# PwrPiSchematics.net
KiCad netlist of a schematic drawn in EasyEDA
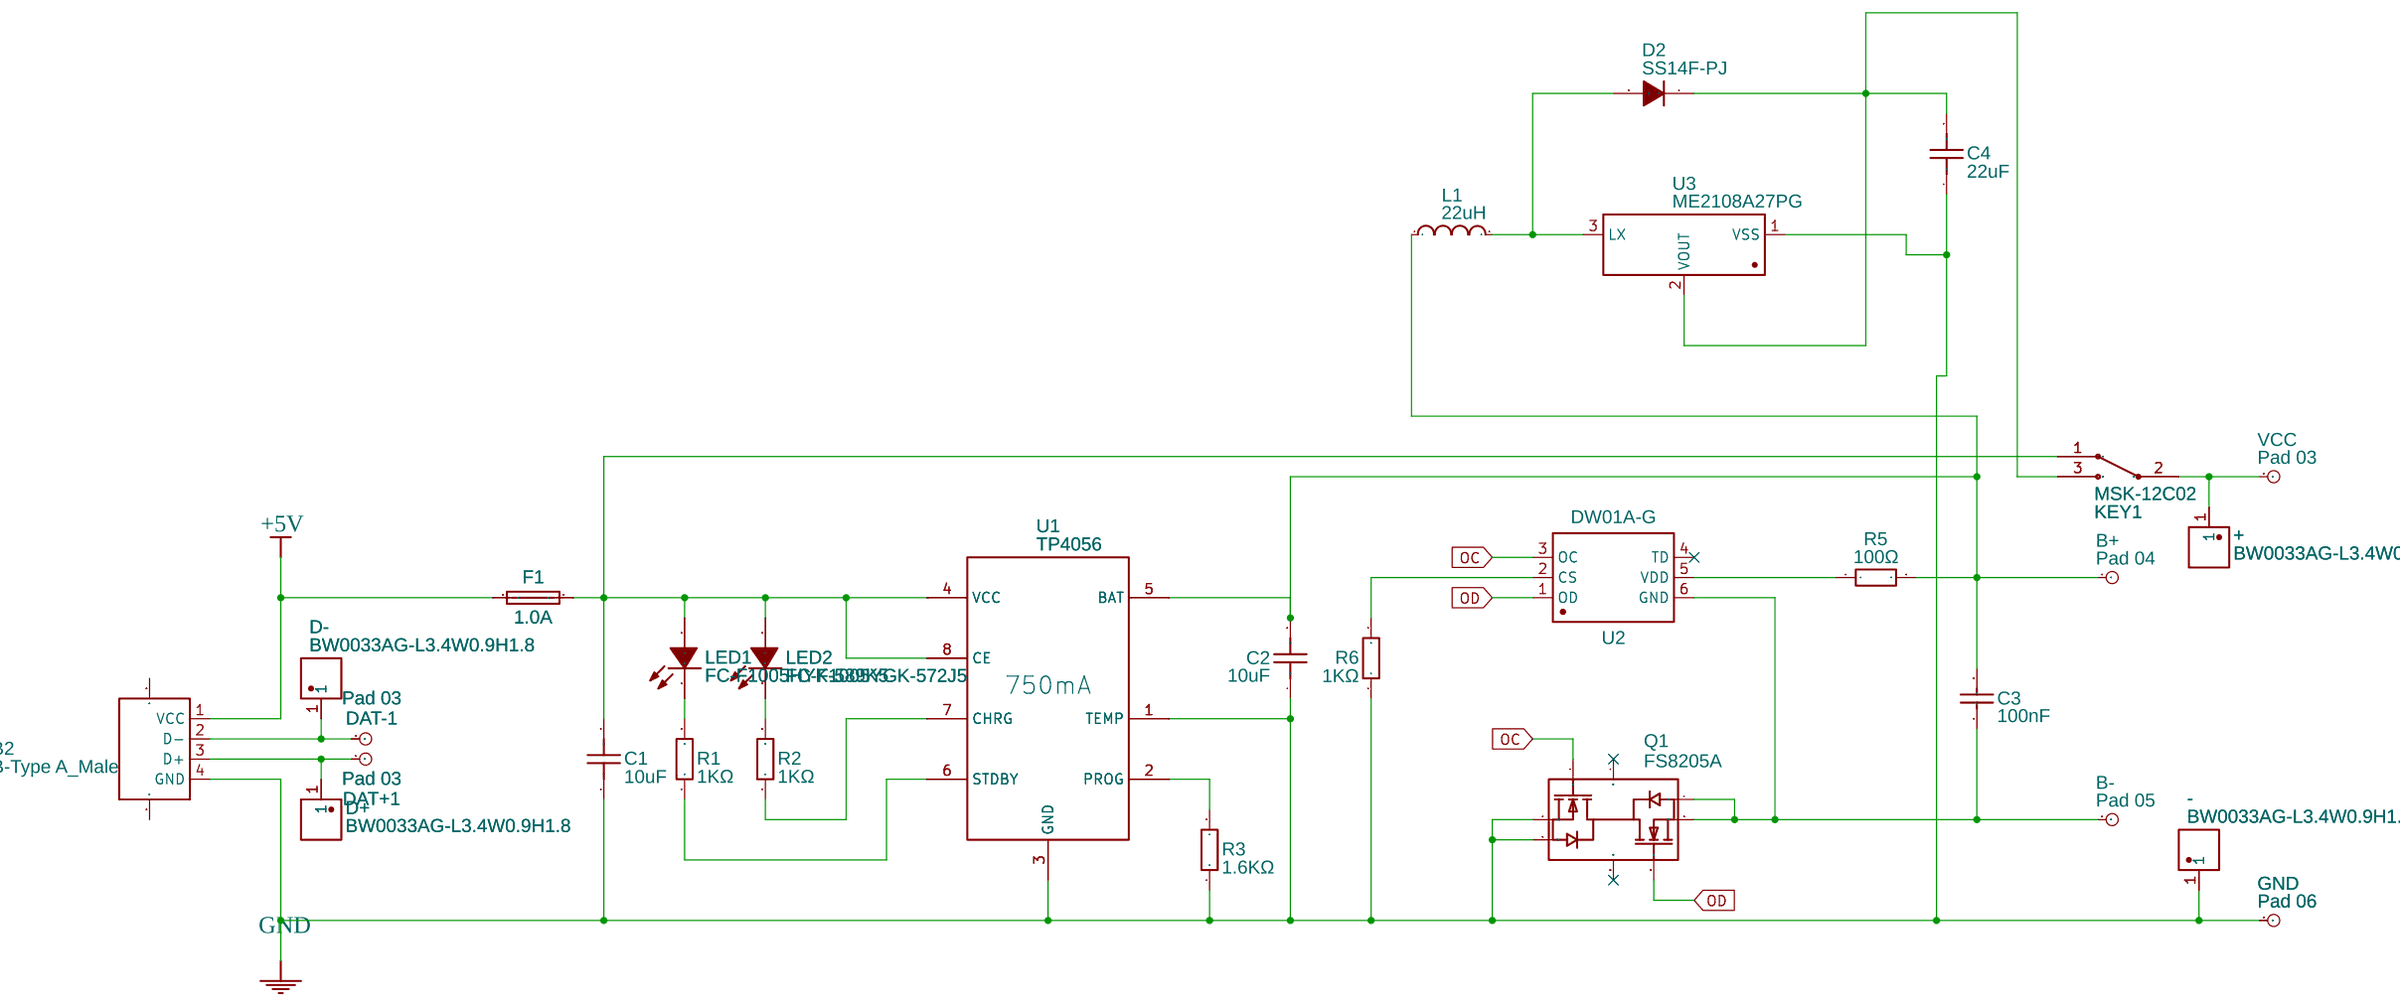
[diagram p0: schematic sheet]

(export (version "E")
  (design (tool "Eeschema 10.0.6"))
  (components
    (comp (ref "+")
      (value "BW0033AG-L3.4W0.9H1.8")
      (fields (field (name "Manufacturer") "BAT WIRELESS(蝙蝠无线)"))
      (libsource (lib "") (part "BW0033AG-L3.4W0.9H1.8_2"))
    )
    (comp (ref "-")
      (value "BW0033AG-L3.4W0.9H1.8")
      (fields (field (name "Manufacturer") "BAT WIRELESS(蝙蝠无线)"))
      (libsource (lib "") (part "BW0033AG-L3.4W0.9H1.8"))
    )
    (comp (ref "B+")
      (value "Pad 04")
      (fields (field (name "Manufacturer Part") "?"))
      (libsource (lib "") (part "Unknown_410_70"))
    )
    (comp (ref "B-")
      (value "Pad 05")
      (fields (field (name "Manufacturer Part") "?"))
      (libsource (lib "") (part "Unknown_410_190"))
    )
    (comp (ref "C1")
      (value "10uF")
      (fields (field (name "Manufacturer Part") "CL10A106MA8NRNC") (field (name "Manufacturer") "SAMSUNG"))
      (libsource (lib "") (part "CL10A106MA8NRNC"))
    )
    (comp (ref "C2")
      (value "10uF")
      (fields (field (name "Manufacturer Part") "CL10A106MA8NRNC") (field (name "Manufacturer") "SAMSUNG"))
      (libsource (lib "") (part "CL10A106MA8NRNC_1"))
    )
    (comp (ref "C3")
      (value "100nF")
      (fields (field (name "Manufacturer Part") "CL05B104KO5NNNC") (field (name "Manufacturer") "SAMSUNG"))
      (libsource (lib "") (part "CL05B104KO5NNNC"))
    )
    (comp (ref "C4")
      (value "22uF")
      (fields
        (field (name "Manufacturer Part") "GRM188R60J226MEA0D")
        (field (name "Manufacturer") "muRata(村田)")
      )
      (libsource (lib "") (part "GRM188R60J226MEA0D"))
    )
    (comp (ref "D+")
      (value "BW0033AG-L3.4W0.9H1.8")
      (fields (field (name "Manufacturer") "BAT WIRELESS(蝙蝠无线)"))
      (libsource (lib "") (part "BW0033AG-L3.4W0.9H1.8_3"))
    )
    (comp (ref "D-")
      (value "BW0033AG-L3.4W0.9H1.8")
      (fields (field (name "Manufacturer") "BAT WIRELESS(蝙蝠无线)"))
      (libsource (lib "") (part "BW0033AG-L3.4W0.9H1.8_1"))
    )
    (comp (ref "D2")
      (value "SS14F-PJ")
      (fields (field (name "Manufacturer") "PJSEMI(平晶微)"))
      (libsource (lib "") (part "SS14F-PJ"))
    )
    (comp (ref "DAT+1")
      (value "Pad 03")
      (fields (field (name "Manufacturer Part") "?"))
      (libsource (lib "") (part "Unknown_-455_160"))
    )
    (comp (ref "DAT-1")
      (value "Pad 03")
      (fields (field (name "Manufacturer Part") "?"))
      (libsource (lib "") (part "Unknown_-455_150"))
    )
    (comp (ref "F1")
      (value "1.0A")
      (fields (field (name "Manufacturer Part") "CFS06V3T1R0") (field (name "Manufacturer") "TA-I Tech"))
      (libsource (lib "") (part "CFS06V3T1R0"))
    )
    (comp (ref "GND")
      (value "Pad 06")
      (fields (field (name "Manufacturer Part") "?"))
      (libsource (lib "") (part "Unknown_490_240"))
    )
    (comp (ref "KEY1")
      (value "MSK-12C02")
      (fields (field (name "Manufacturer Part") "MSK12C02") (field (name "Manufacturer") "SHOU HAN"))
      (libsource (lib "") (part "MSK-12C02"))
    )
    (comp (ref "L1")
      (value "22uH")
      (fields (field (name "Manufacturer Part") "SM3521-220MT") (field (name "Manufacturer") "SXN(顺翔诺)"))
      (libsource (lib "") (part "SM3521-220MT"))
    )
    (comp (ref "LED1")
      (value "FC-F1005HYK-589K5")
      (fields (field (name "Manufacturer") "NATIONSTAR"))
      (libsource (lib "") (part "FC-F1005HYK-589K5"))
    )
    (comp (ref "LED2")
      (value "FC-F1005YGK-572J5")
      (fields (field (name "Manufacturer Part") "NCD0402C1") (field (name "Manufacturer") "国星光电"))
      (libsource (lib "") (part "FC-F1005YGK-572J5"))
    )
    (comp (ref "Q1")
      (value "FS8205A")
      (fields (field (name "Manufacturer") "FORTUNE"))
      (libsource (lib "") (part "Unknown_160_190"))
    )
    (comp (ref "R1")
      (value "1KΩ")
      (fields (field (name "Manufacturer Part") "0402WGF1001TCE") (field (name "Manufacturer") "UniOhm"))
      (libsource (lib "") (part "0402WGF1001TCE"))
    )
    (comp (ref "R2")
      (value "1KΩ")
      (fields (field (name "Manufacturer Part") "0402WGF1001TCE") (field (name "Manufacturer") "UniOhm"))
      (libsource (lib "") (part "0402WGF1001TCE"))
    )
    (comp (ref "R3")
      (value "1.6KΩ")
      (fields (field (name "Manufacturer Part") "0603WAF1601T5E") (field (name "Manufacturer") "UniOhm"))
      (libsource (lib "") (part "0603WAF1601T5E"))
    )
    (comp (ref "R5")
      (value "100Ω")
      (fields (field (name "Manufacturer Part") "0603WAF1000T5E") (field (name "Manufacturer") "UniOhm"))
      (libsource (lib "") (part "0603WAF1000T5E"))
    )
    (comp (ref "R6")
      (value "1KΩ")
      (fields (field (name "Manufacturer Part") "0402WGF1001TCE") (field (name "Manufacturer") "UniOhm"))
      (libsource (lib "") (part "0402WGF1001TCE"))
    )
    (comp (ref "U1")
      (value "TP4056")
      (fields (field (name "Manufacturer") "TOPPOWER"))
      (libsource (lib "") (part "Unknown_-120_140"))
    )
    (comp (ref "U2")
      (value "DW01A-G")
      (fields (field (name "Manufacturer") "FORTUNE"))
      (libsource (lib "") (part "Unknown_160_90"))
    )
    (comp (ref "U3")
      (value "ME2108A27PG")
      (fields (field (name "Manufacturer") "Nanjing Micro One Elec"))
      (libsource (lib "") (part "ME2108A27PG"))
    )
    (comp (ref "USB2")
      (value "USB-Type A_Male")
      (fields (field (name "Manufacturer Part") "USB-05") (field (name "Manufacturer") "SOFNG"))
      (libsource (lib "") (part "USB-Type A_Male"))
    )
    (comp (ref "VCC")
      (value "Pad 03")
      (fields (field (name "Manufacturer Part") "?"))
      (libsource (lib "") (part "Unknown_490_20"))
    )
  )
  (nets
    (net (code "1") (name "+5V") (class "Default")
      (node (ref "F1") (pin "1") (pinfunction "1_1") (pintype "unspecified"))
      (node (ref "USB2") (pin "1") (pinfunction "VCC_1") (pintype "input"))
    )
    (net (code "2") (name "GND") (class "Default")
      (node (ref "-") (pin "1") (pinfunction "1_1") (pintype "unspecified"))
      (node (ref "C1") (pin "1") (pinfunction "1_1") (pintype "unspecified"))
      (node (ref "C2") (pin "1") (pinfunction "1_1") (pintype "unspecified"))
      (node (ref "C4") (pin "1") (pinfunction "1_1") (pintype "unspecified"))
      (node (ref "GND") (pin "P") (pinfunction "P_P") (pintype "unspecified"))
      (node (ref "Q1") (pin "2") (pinfunction "S1_2") (pintype "unspecified"))
      (node (ref "Q1") (pin "3") (pinfunction "S1_3") (pintype "unspecified"))
      (node (ref "R3") (pin "1") (pinfunction "1_1") (pintype "input"))
      (node (ref "R6") (pin "1") (pinfunction "1_1") (pintype "input"))
      (node (ref "U1") (pin "1") (pinfunction "TEMP_1") (pintype "unspecified"))
      (node (ref "U1") (pin "3") (pinfunction "GND_3") (pintype "unspecified"))
      (node (ref "U3") (pin "1") (pinfunction "VSS_1") (pintype "unspecified"))
      (node (ref "USB2") (pin "4") (pinfunction "GND_4") (pintype "input"))
    )
    (net (code "3") (name "Net-(+-Pad1)") (class "Default")
      (node (ref "+") (pin "1") (pinfunction "1_1") (pintype "unspecified"))
      (node (ref "KEY1") (pin "2") (pinfunction "2_2") (pintype "unspecified"))
      (node (ref "VCC") (pin "P") (pinfunction "P_P") (pintype "unspecified"))
    )
    (net (code "4") (name "Net-(D2-A)") (class "Default")
      (node (ref "D2") (pin "2") (pinfunction "A_2") (pintype "unspecified"))
      (node (ref "L1") (pin "2") (pinfunction "2_2") (pintype "unspecified"))
      (node (ref "U3") (pin "3") (pinfunction "LX_3") (pintype "unspecified"))
    )
    (net (code "5") (name "Net-(D2-K)") (class "Default")
      (node (ref "C4") (pin "2") (pinfunction "2_2") (pintype "unspecified"))
      (node (ref "D2") (pin "1") (pinfunction "K_1") (pintype "unspecified"))
      (node (ref "KEY1") (pin "3") (pinfunction "3_3") (pintype "unspecified"))
      (node (ref "U3") (pin "2") (pinfunction "VOUT_2") (pintype "unspecified"))
    )
    (net (code "6") (name "Net-(LED1-A)") (class "Default")
      (node (ref "C1") (pin "2") (pinfunction "2_2") (pintype "unspecified"))
      (node (ref "F1") (pin "2") (pinfunction "2_2") (pintype "unspecified"))
      (node (ref "KEY1") (pin "1") (pinfunction "1_1") (pintype "unspecified"))
      (node (ref "LED1") (pin "2") (pinfunction "A_2") (pintype "unspecified"))
      (node (ref "LED2") (pin "2") (pinfunction "A_2") (pintype "unspecified"))
      (node (ref "U1") (pin "4") (pinfunction "VCC_4") (pintype "unspecified"))
      (node (ref "U1") (pin "8") (pinfunction "CE_8") (pintype "unspecified"))
    )
    (net (code "7") (name "Net-(LED1-K)") (class "Default")
      (node (ref "LED1") (pin "1") (pinfunction "K_1") (pintype "unspecified"))
      (node (ref "R1") (pin "2") (pinfunction "2_2") (pintype "input"))
    )
    (net (code "8") (name "Net-(LED2-K)") (class "Default")
      (node (ref "LED2") (pin "1") (pinfunction "K_1") (pintype "unspecified"))
      (node (ref "R2") (pin "2") (pinfunction "2_2") (pintype "input"))
    )
    (net (code "9") (name "Net-(U1-BAT)") (class "Default")
      (node (ref "B+") (pin "P") (pinfunction "P_P") (pintype "unspecified"))
      (node (ref "C2") (pin "2") (pinfunction "2_2") (pintype "unspecified"))
      (node (ref "C3") (pin "2") (pinfunction "2_2") (pintype "input"))
      (node (ref "L1") (pin "1") (pinfunction "1_1") (pintype "unspecified"))
      (node (ref "R5") (pin "2") (pinfunction "2_2") (pintype "input"))
      (node (ref "U1") (pin "5") (pinfunction "BAT_5") (pintype "unspecified"))
    )
    (net (code "10") (name "Net-(U1-CHRG)") (class "Default")
      (node (ref "R2") (pin "1") (pinfunction "1_1") (pintype "input"))
      (node (ref "U1") (pin "7") (pinfunction "CHRG_7") (pintype "unspecified"))
    )
    (net (code "11") (name "Net-(U1-PROG)") (class "Default")
      (node (ref "R3") (pin "2") (pinfunction "2_2") (pintype "input"))
      (node (ref "U1") (pin "2") (pinfunction "PROG_2") (pintype "unspecified"))
    )
    (net (code "12") (name "Net-(U1-STDBY)") (class "Default")
      (node (ref "R1") (pin "1") (pinfunction "1_1") (pintype "input"))
      (node (ref "U1") (pin "6") (pinfunction "STDBY_6") (pintype "unspecified"))
    )
    (net (code "13") (name "Net-(U2-CS)") (class "Default")
      (node (ref "R6") (pin "2") (pinfunction "2_2") (pintype "input"))
      (node (ref "U2") (pin "2") (pinfunction "CS_2") (pintype "unspecified"))
    )
    (net (code "14") (name "Net-(U2-GND)") (class "Default")
      (node (ref "B-") (pin "P") (pinfunction "P_P") (pintype "unspecified"))
      (node (ref "C3") (pin "1") (pinfunction "1_1") (pintype "input"))
      (node (ref "Q1") (pin "6") (pinfunction "S2_6") (pintype "unspecified"))
      (node (ref "Q1") (pin "7") (pinfunction "S2_7") (pintype "unspecified"))
      (node (ref "U2") (pin "6") (pinfunction "GND_6") (pintype "unspecified"))
    )
    (net (code "15") (name "Net-(U2-VDD)") (class "Default")
      (node (ref "R5") (pin "1") (pinfunction "1_1") (pintype "input"))
      (node (ref "U2") (pin "5") (pinfunction "VDD_5") (pintype "unspecified"))
    )
    (net (code "16") (name "Net-(USB2-D+)") (class "Default")
      (node (ref "D+") (pin "1") (pinfunction "1_1") (pintype "unspecified"))
      (node (ref "DAT+1") (pin "P") (pinfunction "P_P") (pintype "unspecified"))
      (node (ref "USB2") (pin "3") (pinfunction "D+_3") (pintype "input"))
    )
    (net (code "17") (name "Net-(USB2-D-)") (class "Default")
      (node (ref "D-") (pin "1") (pinfunction "1_1") (pintype "unspecified"))
      (node (ref "DAT-1") (pin "P") (pinfunction "P_P") (pintype "unspecified"))
      (node (ref "USB2") (pin "2") (pinfunction "D-_2") (pintype "input"))
    )
    (net (code "18") (name "OC") (class "Default")
      (node (ref "Q1") (pin "4") (pinfunction "G1_4") (pintype "unspecified"))
      (node (ref "U2") (pin "3") (pinfunction "OC_3") (pintype "unspecified"))
    )
    (net (code "19") (name "OD") (class "Default")
      (node (ref "Q1") (pin "5") (pinfunction "G2_5") (pintype "unspecified"))
      (node (ref "U2") (pin "1") (pinfunction "OD_1") (pintype "unspecified"))
    )
    (net (code "20") (name "unconnected-(Q1-D12-Pad1)") (class "Default")
      (node (ref "Q1") (pin "1") (pinfunction "D12_1") (pintype "unspecified+no_connect"))
    )
    (net (code "21") (name "unconnected-(Q1-D12-Pad8)") (class "Default")
      (node (ref "Q1") (pin "8") (pinfunction "D12_8") (pintype "unspecified+no_connect"))
    )
    (net (code "22") (name "unconnected-(U2-TD-Pad4)") (class "Default")
      (node (ref "U2") (pin "4") (pinfunction "TD_4") (pintype "unspecified+no_connect"))
    )
    (net (code "23") (name "unconnected-(USB2-Pad5)") (class "Default")
      (node (ref "USB2") (pin "5") (pinfunction "5_5") (pintype "unspecified"))
    )
    (net (code "24") (name "unconnected-(USB2-Pad6)") (class "Default")
      (node (ref "USB2") (pin "6") (pinfunction "6_6") (pintype "unspecified"))
    )
  )
)
